# afe.net
KiCad netlist of a schematic drawn in EAGLE
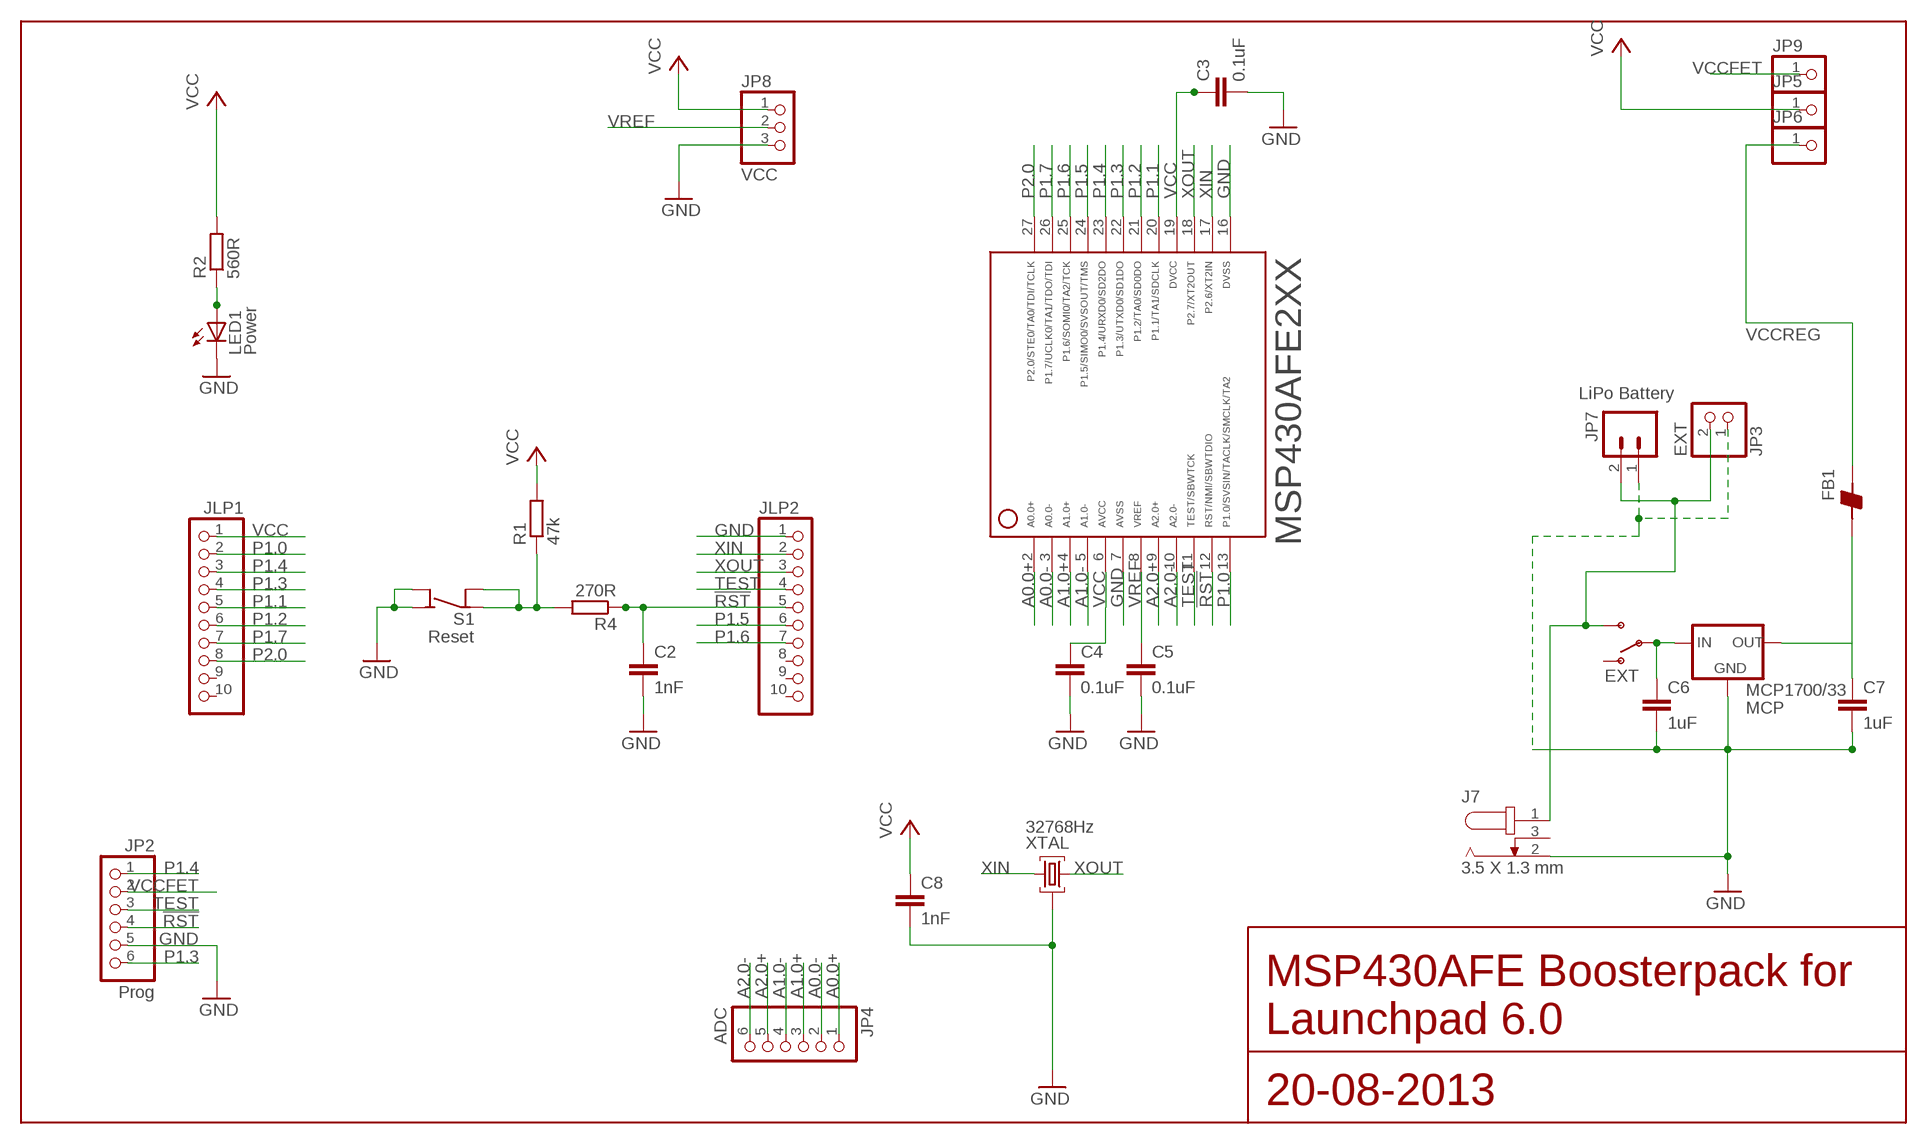
[diagram p0: schematic, sheet 1]

(export (version "E")
  (design (tool "Eeschema 10.0.6"))
  (components
    (comp (ref "C2")
      (value "1nF")
      (footprint "eagle-import:C0805")
      (libsource (lib "eagle-import") (part "C-EUC0805"))
    )
    (comp (ref "C3")
      (value "0.1uF")
      (footprint "eagle-import:C0805")
      (libsource (lib "eagle-import") (part "C-EUC0805"))
    )
    (comp (ref "C4")
      (value "0.1uF")
      (footprint "eagle-import:C0805")
      (libsource (lib "eagle-import") (part "C-EUC0805"))
    )
    (comp (ref "C5")
      (value "0.1uF")
      (footprint "eagle-import:C0805")
      (libsource (lib "eagle-import") (part "C-EUC0805"))
    )
    (comp (ref "C6")
      (value "1uF")
      (footprint "eagle-import:C0805")
      (libsource (lib "eagle-import") (part "C-EUC0805"))
    )
    (comp (ref "C7")
      (value "1uF")
      (footprint "eagle-import:C0805")
      (libsource (lib "eagle-import") (part "C-EUC0805"))
    )
    (comp (ref "C8")
      (value "1nF")
      (footprint "eagle-import:C0805")
      (libsource (lib "eagle-import") (part "C-EUC0805"))
    )
    (comp (ref "FB1")
      (value "BEAD-0805")
      (footprint "eagle-import:0805")
      (libsource (lib "eagle-import") (part "BEAD-0805"))
    )
    (comp (ref "J7")
      (value "3.5 X 1.3 mm")
      (footprint "eagle-import:3.5X1.3MM_DC_JACK")
      (libsource (lib "eagle-import") (part "DC_JACK_3.5X1.3MM"))
    )
    (comp (ref "JLP1")
      (value "PH1X10OCT076")
      (footprint "eagle-import:PH1X10OCT76")
      (libsource (lib "eagle-import") (part "PH1X10OCT076"))
    )
    (comp (ref "JLP2")
      (value "PH1X10OCT076")
      (footprint "eagle-import:PH1X10OCT76")
      (libsource (lib "eagle-import") (part "PH1X10OCT076"))
    )
    (comp (ref "JP2")
      (value "Prog")
      (footprint "eagle-import:1X06")
      (libsource (lib "eagle-import") (part "PINHD-1X6"))
    )
    (comp (ref "JP3")
      (value "EXT")
      (footprint "eagle-import:1X02")
      (libsource (lib "eagle-import") (part "PINHD-1X2"))
    )
    (comp (ref "JP4")
      (value "ADC")
      (footprint "eagle-import:1X06")
      (libsource (lib "eagle-import") (part "PINHD-1X6"))
    )
    (comp (ref "JP5")
      (value "PINHD-1X1")
      (footprint "eagle-import:1X01")
      (libsource (lib "eagle-import") (part "PINHD-1X1"))
    )
    (comp (ref "JP6")
      (value "PINHD-1X1")
      (footprint "eagle-import:1X01")
      (libsource (lib "eagle-import") (part "PINHD-1X1"))
    )
    (comp (ref "JP7")
      (value "LiPo Battery")
      (footprint "eagle-import:JST-2-PTH")
      (libsource (lib "eagle-import") (part "M02JST-PTH-2"))
    )
    (comp (ref "JP8")
      (value "VCC")
      (footprint "eagle-import:1X03")
      (libsource (lib "eagle-import") (part "PINHD-1X3"))
    )
    (comp (ref "JP9")
      (value "PINHD-1X1")
      (footprint "eagle-import:1X01")
      (libsource (lib "eagle-import") (part "PINHD-1X1"))
    )
    (comp (ref "LED1")
      (value "Power")
      (footprint "eagle-import:CHIPLED_1206")
      (libsource (lib "eagle-import") (part "LEDCHIPLED_1206"))
    )
    (comp (ref "MCP1700/33")
      (value "MCP")
      (footprint "eagle-import:SOT-23")
      (libsource (lib "eagle-import") (part "MCP1700SOT-23"))
    )
    (comp (ref "MSP430AFE")
      (value "AFE2XX--PW24")
      (footprint "eagle-import:PW24")
      (libsource (lib "eagle-import") (part "AFE2XX--PW24"))
    )
    (comp (ref "ON")
      (value "EXT")
      (footprint "eagle-import:SWITCH-SPDT")
      (libsource (lib "eagle-import") (part "SWITCH-SPSTPTH"))
    )
    (comp (ref "R1")
      (value "47k")
      (footprint "eagle-import:R0805")
      (libsource (lib "eagle-import") (part "R-EU_R0805"))
    )
    (comp (ref "R2")
      (value "560R")
      (footprint "eagle-import:R0805")
      (libsource (lib "eagle-import") (part "R-EU_R0805"))
    )
    (comp (ref "R4")
      (value "270R")
      (footprint "eagle-import:R0805")
      (libsource (lib "eagle-import") (part "R-EU_R0805"))
    )
    (comp (ref "S1")
      (value "Reset")
      (footprint "eagle-import:6MMTACTILE_4PIN")
      (libsource (lib "eagle-import") (part "SPST4"))
    )
    (comp (ref "XTAL")
      (value "32768Hz")
      (footprint "eagle-import:QUARZ5")
      (libsource (lib "eagle-import") (part "QUARZ5"))
    )
  )
  (nets
    (net (code "1") (name "A0.0+") (class "Default")
      (node (ref "JP4") (pin "1") (pinfunction "1_1") (pintype "passive"))
      (node (ref "MSP430AFE") (pin "2") (pinfunction "1_2") (pintype "bidirectional"))
    )
    (net (code "2") (name "A0.0-") (class "Default")
      (node (ref "JP4") (pin "2") (pinfunction "2_2") (pintype "passive"))
      (node (ref "MSP430AFE") (pin "3") (pinfunction "2_3") (pintype "bidirectional"))
    )
    (net (code "3") (name "A1.0+") (class "Default")
      (node (ref "JP4") (pin "3") (pinfunction "3_3") (pintype "passive"))
      (node (ref "MSP430AFE") (pin "4") (pinfunction "3_4") (pintype "bidirectional"))
    )
    (net (code "4") (name "A1.0-") (class "Default")
      (node (ref "JP4") (pin "4") (pinfunction "4_4") (pintype "passive"))
      (node (ref "MSP430AFE") (pin "5") (pinfunction "4_5") (pintype "bidirectional"))
    )
    (net (code "5") (name "A2.0+") (class "Default")
      (node (ref "JP4") (pin "5") (pinfunction "5_5") (pintype "passive"))
      (node (ref "MSP430AFE") (pin "9") (pinfunction "8_9") (pintype "bidirectional"))
    )
    (net (code "6") (name "A2.0-") (class "Default")
      (node (ref "JP4") (pin "6") (pinfunction "6_6") (pintype "passive"))
      (node (ref "MSP430AFE") (pin "10") (pinfunction "9_10") (pintype "bidirectional"))
    )
    (net (code "7") (name "GND") (class "Default")
      (node (ref "C2") (pin "2") (pinfunction "2_2") (pintype "passive"))
      (node (ref "C3") (pin "2") (pinfunction "2_2") (pintype "passive"))
      (node (ref "C4") (pin "2") (pinfunction "2_2") (pintype "passive"))
      (node (ref "C5") (pin "2") (pinfunction "2_2") (pintype "passive"))
      (node (ref "C6") (pin "2") (pinfunction "2_2") (pintype "passive"))
      (node (ref "C7") (pin "2") (pinfunction "2_2") (pintype "passive"))
      (node (ref "C8") (pin "2") (pinfunction "2_2") (pintype "passive"))
      (node (ref "J7") (pin "2") (pinfunction "2_2") (pintype "passive"))
      (node (ref "JLP2") (pin "1") (pinfunction "1_1") (pintype "passive"))
      (node (ref "JP2") (pin "5") (pinfunction "5_5") (pintype "passive"))
      (node (ref "JP3") (pin "1") (pinfunction "1_1") (pintype "passive"))
      (node (ref "JP7") (pin "1") (pinfunction "1_1") (pintype "passive"))
      (node (ref "JP8") (pin "3") (pinfunction "3_3") (pintype "passive"))
      (node (ref "LED1") (pin "C") (pinfunction "C_C") (pintype "passive"))
      (node (ref "MCP1700/33") (pin "1") (pinfunction "GND_1") (pintype "input"))
      (node (ref "MSP430AFE") (pin "16") (pinfunction "13_16") (pintype "power_in"))
      (node (ref "MSP430AFE") (pin "7") (pinfunction "6_7") (pintype "power_in"))
      (node (ref "S1") (pin "A1") (pinfunction "NO_A1") (pintype "passive"))
      (node (ref "S1") (pin "A2") (pinfunction "NO_A2") (pintype "passive"))
      (node (ref "XTAL") (pin "GND@0") (pinfunction "0_GND@0") (pintype "passive"))
    )
    (net (code "8") (name "Net-(FB1-P$1)") (class "Default")
      (node (ref "C7") (pin "1") (pinfunction "1_1") (pintype "passive"))
      (node (ref "FB1") (pin "1") (pinfunction "P$1_1") (pintype "passive"))
      (node (ref "MCP1700/33") (pin "2") (pinfunction "OUT_2") (pintype "passive"))
    )
    (net (code "9") (name "Net-(LED1-PadA)") (class "Default")
      (node (ref "LED1") (pin "A") (pinfunction "A_A") (pintype "passive"))
      (node (ref "R2") (pin "1") (pinfunction "1_1") (pintype "passive"))
    )
    (net (code "10") (name "Net-(MCP1700/33-IN)") (class "Default")
      (node (ref "C6") (pin "1") (pinfunction "1_1") (pintype "passive"))
      (node (ref "MCP1700/33") (pin "3") (pinfunction "IN_3") (pintype "input"))
      (node (ref "ON") (pin "2") (pinfunction "P_2") (pintype "passive"))
    )
    (net (code "11") (name "Net-(ON-S)") (class "Default")
      (node (ref "J7") (pin "1") (pinfunction "1_1") (pintype "passive"))
      (node (ref "JP3") (pin "2") (pinfunction "2_2") (pintype "passive"))
      (node (ref "JP7") (pin "2") (pinfunction "2_2") (pintype "passive"))
      (node (ref "ON") (pin "3") (pinfunction "S_3") (pintype "passive"))
    )
    (net (code "12") (name "Net-(R1-Pad1)") (class "Default")
      (node (ref "R1") (pin "1") (pinfunction "1_1") (pintype "passive"))
      (node (ref "R4") (pin "2") (pinfunction "2_2") (pintype "passive"))
      (node (ref "S1") (pin "B1") (pinfunction "COM_B1") (pintype "passive"))
      (node (ref "S1") (pin "B2") (pinfunction "COM_B2") (pintype "passive"))
    )
    (net (code "13") (name "P1.0") (class "Default")
      (node (ref "JLP1") (pin "2") (pinfunction "2_2") (pintype "passive"))
      (node (ref "MSP430AFE") (pin "13") (pinfunction "12_13") (pintype "bidirectional"))
    )
    (net (code "14") (name "P1.1") (class "Default")
      (node (ref "JLP1") (pin "5") (pinfunction "5_5") (pintype "passive"))
      (node (ref "MSP430AFE") (pin "20") (pinfunction "17_20") (pintype "bidirectional"))
    )
    (net (code "15") (name "P1.2") (class "Default")
      (node (ref "JLP1") (pin "6") (pinfunction "6_6") (pintype "passive"))
      (node (ref "MSP430AFE") (pin "21") (pinfunction "18_21") (pintype "bidirectional"))
    )
    (net (code "16") (name "P1.3") (class "Default")
      (node (ref "JLP1") (pin "4") (pinfunction "4_4") (pintype "passive"))
      (node (ref "JP2") (pin "6") (pinfunction "6_6") (pintype "passive"))
      (node (ref "MSP430AFE") (pin "22") (pinfunction "19_22") (pintype "bidirectional"))
    )
    (net (code "17") (name "P1.4") (class "Default")
      (node (ref "JLP1") (pin "3") (pinfunction "3_3") (pintype "passive"))
      (node (ref "JP2") (pin "1") (pinfunction "1_1") (pintype "passive"))
      (node (ref "MSP430AFE") (pin "23") (pinfunction "20_23") (pintype "bidirectional"))
    )
    (net (code "18") (name "P1.5") (class "Default")
      (node (ref "JLP2") (pin "6") (pinfunction "6_6") (pintype "passive"))
      (node (ref "MSP430AFE") (pin "24") (pinfunction "21_24") (pintype "bidirectional"))
    )
    (net (code "19") (name "P1.6") (class "Default")
      (node (ref "JLP2") (pin "7") (pinfunction "7_7") (pintype "passive"))
      (node (ref "MSP430AFE") (pin "25") (pinfunction "22_25") (pintype "bidirectional"))
    )
    (net (code "20") (name "P1.7") (class "Default")
      (node (ref "JLP1") (pin "7") (pinfunction "7_7") (pintype "passive"))
      (node (ref "MSP430AFE") (pin "26") (pinfunction "23_26") (pintype "bidirectional"))
    )
    (net (code "21") (name "P2.0") (class "Default")
      (node (ref "JLP1") (pin "8") (pinfunction "8_8") (pintype "passive"))
      (node (ref "MSP430AFE") (pin "27") (pinfunction "24_27") (pintype "bidirectional"))
    )
    (net (code "22") (name "TEST") (class "Default")
      (node (ref "JLP2") (pin "4") (pinfunction "4_4") (pintype "passive"))
      (node (ref "JP2") (pin "3") (pinfunction "3_3") (pintype "passive"))
      (node (ref "MSP430AFE") (pin "11") (pinfunction "10_11") (pintype "bidirectional"))
    )
    (net (code "23") (name "VCC") (class "Default")
      (node (ref "C3") (pin "1") (pinfunction "1_1") (pintype "passive"))
      (node (ref "C4") (pin "1") (pinfunction "1_1") (pintype "passive"))
      (node (ref "C8") (pin "1") (pinfunction "1_1") (pintype "passive"))
      (node (ref "JLP1") (pin "1") (pinfunction "1_1") (pintype "passive"))
      (node (ref "JP5") (pin "1") (pinfunction "1_1") (pintype "passive"))
      (node (ref "JP8") (pin "1") (pinfunction "1_1") (pintype "passive"))
      (node (ref "MSP430AFE") (pin "19") (pinfunction "16_19") (pintype "power_in"))
      (node (ref "MSP430AFE") (pin "6") (pinfunction "5_6") (pintype "power_in"))
      (node (ref "R1") (pin "2") (pinfunction "2_2") (pintype "passive"))
      (node (ref "R2") (pin "2") (pinfunction "2_2") (pintype "passive"))
    )
    (net (code "24") (name "VCCFET") (class "Default")
      (node (ref "JP2") (pin "2") (pinfunction "2_2") (pintype "passive"))
      (node (ref "JP9") (pin "1") (pinfunction "1_1") (pintype "passive"))
    )
    (net (code "25") (name "VCCREG") (class "Default")
      (node (ref "FB1") (pin "2") (pinfunction "P$2_2") (pintype "passive"))
      (node (ref "JP6") (pin "1") (pinfunction "1_1") (pintype "passive"))
    )
    (net (code "26") (name "VREF") (class "Default")
      (node (ref "C5") (pin "1") (pinfunction "1_1") (pintype "passive"))
      (node (ref "JP8") (pin "2") (pinfunction "2_2") (pintype "passive"))
      (node (ref "MSP430AFE") (pin "8") (pinfunction "7_8") (pintype "bidirectional"))
    )
    (net (code "27") (name "XIN") (class "Default")
      (node (ref "JLP2") (pin "2") (pinfunction "2_2") (pintype "passive"))
      (node (ref "MSP430AFE") (pin "17") (pinfunction "14_17") (pintype "bidirectional"))
      (node (ref "XTAL") (pin "2") (pinfunction "2_2") (pintype "passive"))
    )
    (net (code "28") (name "XOUT") (class "Default")
      (node (ref "JLP2") (pin "3") (pinfunction "3_3") (pintype "passive"))
      (node (ref "MSP430AFE") (pin "18") (pinfunction "15_18") (pintype "bidirectional"))
      (node (ref "XTAL") (pin "1") (pinfunction "1_1") (pintype "passive"))
    )
    (net (code "29") (name "unconnected-(J7-Pad3)") (class "Default")
      (node (ref "J7") (pin "3") (pinfunction "3_3") (pintype "passive"))
    )
    (net (code "30") (name "unconnected-(JLP1-Pad9)") (class "Default")
      (node (ref "JLP1") (pin "9") (pinfunction "9_9") (pintype "passive"))
    )
    (net (code "31") (name "unconnected-(JLP1-Pad10)") (class "Default")
      (node (ref "JLP1") (pin "10") (pinfunction "10_10") (pintype "passive"))
    )
    (net (code "32") (name "unconnected-(JLP2-Pad8)") (class "Default")
      (node (ref "JLP2") (pin "8") (pinfunction "8_8") (pintype "passive"))
    )
    (net (code "33") (name "unconnected-(JLP2-Pad9)") (class "Default")
      (node (ref "JLP2") (pin "9") (pinfunction "9_9") (pintype "passive"))
    )
    (net (code "34") (name "unconnected-(JLP2-Pad10)") (class "Default")
      (node (ref "JLP2") (pin "10") (pinfunction "10_10") (pintype "passive"))
    )
    (net (code "35") (name "unconnected-(ON-O-Pad1)") (class "Default")
      (node (ref "ON") (pin "1") (pinfunction "O_1") (pintype "passive"))
    )
    (net (code "36") (name "~{RST}") (class "Default")
      (node (ref "C2") (pin "1") (pinfunction "1_1") (pintype "passive"))
      (node (ref "JLP2") (pin "5") (pinfunction "5_5") (pintype "passive"))
      (node (ref "JP2") (pin "4") (pinfunction "4_4") (pintype "passive"))
      (node (ref "MSP430AFE") (pin "12") (pinfunction "11_12") (pintype "bidirectional"))
      (node (ref "R4") (pin "1") (pinfunction "1_1") (pintype "passive"))
    )
  )
)
